# EAGLEPCBFINAL.net
KiCad netlist of a schematic drawn in EAGLE
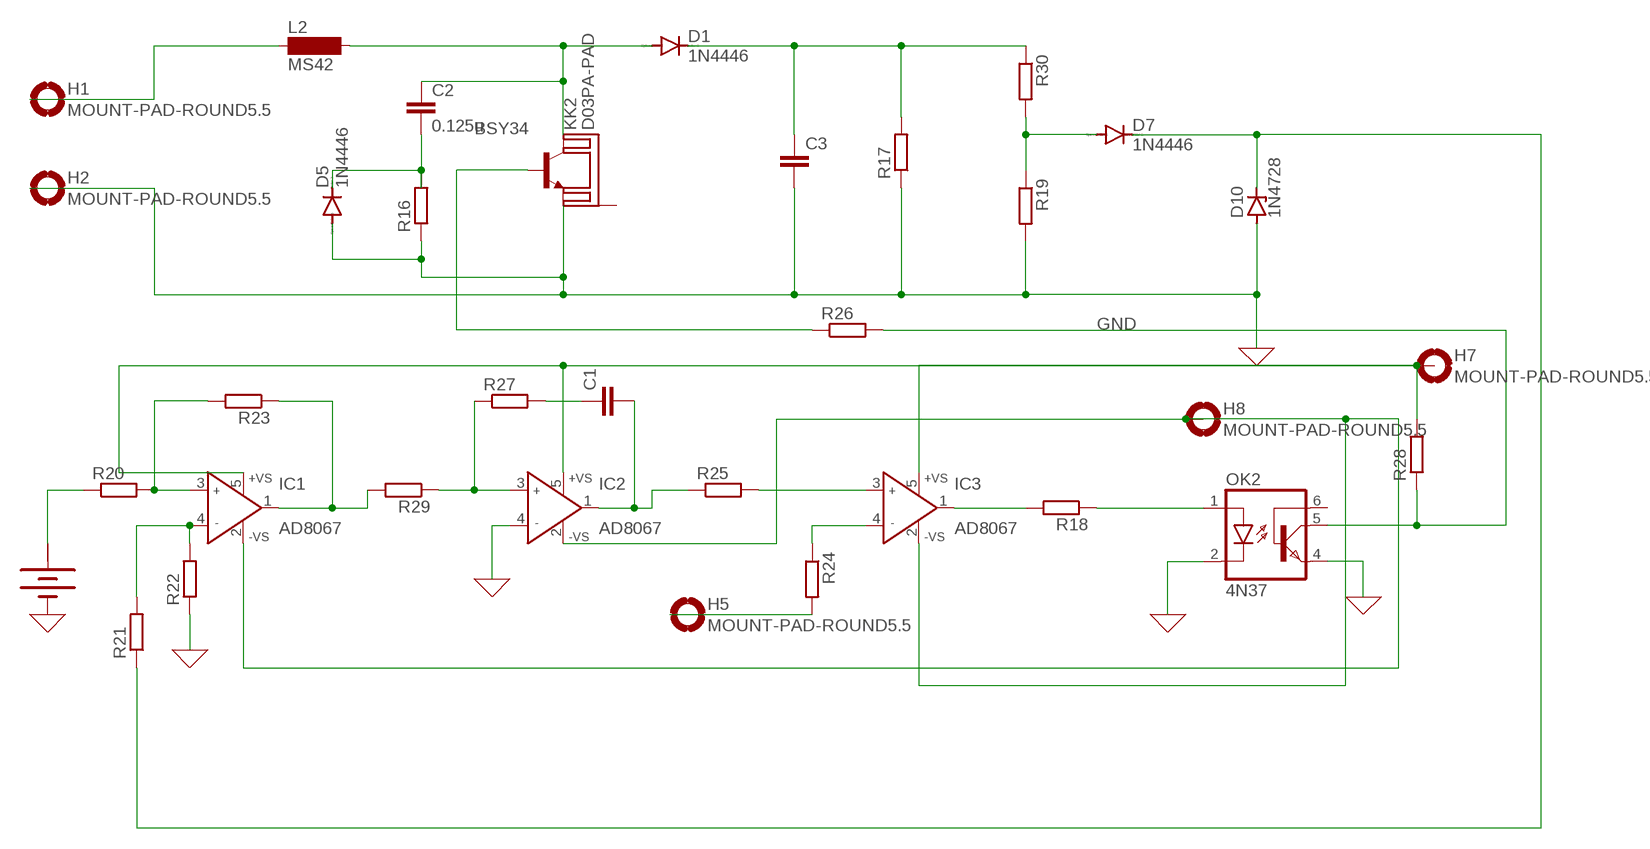
[diagram p0: schematic, sheet 1]

(export (version "E")
  (design (tool "Eeschema 10.0.6"))
  (components
    (comp (ref "BAT1")
      (value "BATTERY")
      (footprint "eagle-import:BATTERY")
      (libsource (lib "eagle-import") (part "BATTERY"))
    )
    (comp (ref "C1")
      (value "C2.5/2")
      (footprint "eagle-import:C2.5-2")
      (libsource (lib "eagle-import") (part "C2.5/2"))
    )
    (comp (ref "C2")
      (value "0.125u")
      (footprint "eagle-import:C5B3.5")
      (libsource (lib "eagle-import") (part "C5/3.5"))
    )
    (comp (ref "C3")
      (value "C7.5/3")
      (footprint "eagle-import:C7.5B3")
      (libsource (lib "eagle-import") (part "C7.5/3"))
    )
    (comp (ref "D1")
      (value "1N4446")
      (footprint "eagle-import:DO35-10")
      (libsource (lib "eagle-import") (part "1N4446"))
    )
    (comp (ref "D5")
      (value "1N4446")
      (footprint "eagle-import:DO35-10")
      (libsource (lib "eagle-import") (part "1N4446"))
    )
    (comp (ref "D7")
      (value "1N4446")
      (footprint "eagle-import:DO35-10")
      (libsource (lib "eagle-import") (part "1N4446"))
    )
    (comp (ref "D10")
      (value "1N4728")
      (footprint "eagle-import:DO41Z10")
      (libsource (lib "eagle-import") (part "1N4728"))
    )
    (comp (ref "H1")
      (value "MOUNT-PAD-ROUND5.5")
      (footprint "eagle-import:5,5-PAD")
      (libsource (lib "eagle-import") (part "MOUNT-PAD-ROUND5.5"))
    )
    (comp (ref "H2")
      (value "MOUNT-PAD-ROUND5.5")
      (footprint "eagle-import:5,5-PAD")
      (libsource (lib "eagle-import") (part "MOUNT-PAD-ROUND5.5"))
    )
    (comp (ref "H5")
      (value "MOUNT-PAD-ROUND5.5")
      (footprint "eagle-import:5,5-PAD")
      (libsource (lib "eagle-import") (part "MOUNT-PAD-ROUND5.5"))
    )
    (comp (ref "H7")
      (value "MOUNT-PAD-ROUND5.5")
      (footprint "eagle-import:5,5-PAD")
      (libsource (lib "eagle-import") (part "MOUNT-PAD-ROUND5.5"))
    )
    (comp (ref "H8")
      (value "MOUNT-PAD-ROUND5.5")
      (footprint "eagle-import:5,5-PAD")
      (libsource (lib "eagle-import") (part "MOUNT-PAD-ROUND5.5"))
    )
    (comp (ref "IC1")
      (value "AD8067")
      (footprint "eagle-import:SOT23-5")
      (fields (field (name "MF") "ALTERA CORPORATION") (field (name "MPN") "AD8067ARTZ-REEL7"))
      (libsource (lib "eagle-import") (part "AD8067"))
    )
    (comp (ref "IC2")
      (value "AD8067")
      (footprint "eagle-import:SOT23-5")
      (fields (field (name "MF") "ALTERA CORPORATION") (field (name "MPN") "AD8067ARTZ-REEL7"))
      (libsource (lib "eagle-import") (part "AD8067"))
    )
    (comp (ref "IC3")
      (value "AD8067")
      (footprint "eagle-import:SOT23-5")
      (fields (field (name "MF") "ALTERA CORPORATION") (field (name "MPN") "AD8067ARTZ-REEL7"))
      (libsource (lib "eagle-import") (part "AD8067"))
    )
    (comp (ref "KK2")
      (value "D03PA-PAD")
      (footprint "eagle-import:D03PA-PAD")
      (libsource (lib "eagle-import") (part "D03PA-PAD"))
    )
    (comp (ref "L2")
      (value "MS42")
      (footprint "eagle-import:MS42")
      (libsource (lib "eagle-import") (part "MS42"))
    )
    (comp (ref "OK2")
      (value "4N37")
      (footprint "eagle-import:DIL06")
      (fields (field (name "MF") "FAIRCHILD SEMICONDUCTOR"))
      (libsource (lib "eagle-import") (part "4N37"))
    )
    (comp (ref "R16")
      (value "R-EU_0204/2V")
      (footprint "eagle-import:0204V")
      (libsource (lib "eagle-import") (part "R-EU_0204/2V"))
    )
    (comp (ref "R17")
      (value "R-EU_0204/2V")
      (footprint "eagle-import:0204V")
      (libsource (lib "eagle-import") (part "R-EU_0204/2V"))
    )
    (comp (ref "R18")
      (value "R-EU_0204/5")
      (footprint "eagle-import:0204_5")
      (libsource (lib "eagle-import") (part "R-EU_0204/5"))
    )
    (comp (ref "R19")
      (value "R-EU_0207/10")
      (footprint "eagle-import:0207_10")
      (libsource (lib "eagle-import") (part "R-EU_0207/10"))
    )
    (comp (ref "R20")
      (value "R-EU_0207/10")
      (footprint "eagle-import:0207_10")
      (libsource (lib "eagle-import") (part "R-EU_0207/10"))
    )
    (comp (ref "R21")
      (value "R-EU_0207/10")
      (footprint "eagle-import:0207_10")
      (libsource (lib "eagle-import") (part "R-EU_0207/10"))
    )
    (comp (ref "R22")
      (value "R-EU_0207/10")
      (footprint "eagle-import:0207_10")
      (libsource (lib "eagle-import") (part "R-EU_0207/10"))
    )
    (comp (ref "R23")
      (value "R-EU_0207/10")
      (footprint "eagle-import:0207_10")
      (libsource (lib "eagle-import") (part "R-EU_0207/10"))
    )
    (comp (ref "R24")
      (value "R-EU_0207/10")
      (footprint "eagle-import:0207_10")
      (libsource (lib "eagle-import") (part "R-EU_0207/10"))
    )
    (comp (ref "R25")
      (value "R-EU_0207/10")
      (footprint "eagle-import:0207_10")
      (libsource (lib "eagle-import") (part "R-EU_0207/10"))
    )
    (comp (ref "R26")
      (value "R-EU_0207/10")
      (footprint "eagle-import:0207_10")
      (libsource (lib "eagle-import") (part "R-EU_0207/10"))
    )
    (comp (ref "R27")
      (value "R-EU_0309/12")
      (footprint "eagle-import:0309_12")
      (libsource (lib "eagle-import") (part "R-EU_0309/12"))
    )
    (comp (ref "R28")
      (value "R-EU_0411/15")
      (footprint "eagle-import:0411_15")
      (libsource (lib "eagle-import") (part "R-EU_0411/15"))
    )
    (comp (ref "R29")
      (value "R-EU_0411/15")
      (footprint "eagle-import:0411_15")
      (libsource (lib "eagle-import") (part "R-EU_0411/15"))
    )
    (comp (ref "R30")
      (value "R-EU_0922/22")
      (footprint "eagle-import:0922_22")
      (libsource (lib "eagle-import") (part "R-EU_0922/22"))
    )
    (comp (ref "T1")
      (value "BSY34")
      (footprint "eagle-import:TO39")
      (libsource (lib "eagle-import") (part "BSY34"))
    )
  )
  (nets
    (net (code "1") (name "/+") (class "Default")
      (node (ref "BAT1") (pin "+@1") (pinfunction "+_+@1") (pintype "power_in"))
    )
    (net (code "2") (name "GND") (class "Default")
      (node (ref "BAT1") (pin "-") (pinfunction "-_-") (pintype "power_in"))
      (node (ref "C3") (pin "2") (pinfunction "2_2") (pintype "passive"))
      (node (ref "D10") (pin "A") (pinfunction "A_A") (pintype "passive"))
      (node (ref "D5") (pin "A") (pinfunction "A_A") (pintype "passive"))
      (node (ref "H2") (pin "B5,5") (pinfunction "MOUNT_B5,5") (pintype "passive"))
      (node (ref "IC2") (pin "4") (pinfunction "IN-_4") (pintype "input"))
      (node (ref "OK2") (pin "2") (pinfunction "C_2") (pintype "passive"))
      (node (ref "OK2") (pin "4") (pinfunction "EMI_4") (pintype "passive"))
      (node (ref "R16") (pin "1") (pinfunction "1_1") (pintype "passive"))
      (node (ref "R17") (pin "1") (pinfunction "1_1") (pintype "passive"))
      (node (ref "R19") (pin "2") (pinfunction "2_2") (pintype "passive"))
      (node (ref "R22") (pin "1") (pinfunction "1_1") (pintype "passive"))
      (node (ref "T1") (pin "1") (pinfunction "E_1") (pintype "passive"))
    )
    (net (code "3") (name "Net-(BAT1-Pad+)") (class "Default")
      (node (ref "BAT1") (pin "+") (pinfunction "+_+") (pintype "power_in"))
      (node (ref "R20") (pin "1") (pinfunction "1_1") (pintype "passive"))
    )
    (net (code "4") (name "Net-(C1-Pad1)") (class "Default")
      (node (ref "C1") (pin "1") (pinfunction "1_1") (pintype "passive"))
      (node (ref "R27") (pin "2") (pinfunction "2_2") (pintype "passive"))
    )
    (net (code "5") (name "Net-(C2-Pad2)") (class "Default")
      (node (ref "C2") (pin "2") (pinfunction "2_2") (pintype "passive"))
      (node (ref "D5") (pin "C") (pinfunction "C_C") (pintype "passive"))
      (node (ref "R16") (pin "2") (pinfunction "2_2") (pintype "passive"))
    )
    (net (code "6") (name "Net-(C3-Pad1)") (class "Default")
      (node (ref "C3") (pin "1") (pinfunction "1_1") (pintype "passive"))
      (node (ref "D1") (pin "C") (pinfunction "C_C") (pintype "passive"))
      (node (ref "R17") (pin "2") (pinfunction "2_2") (pintype "passive"))
      (node (ref "R30") (pin "1") (pinfunction "1_1") (pintype "passive"))
    )
    (net (code "7") (name "Net-(D7-PadA)") (class "Default")
      (node (ref "D7") (pin "A") (pinfunction "A_A") (pintype "passive"))
      (node (ref "R19") (pin "1") (pinfunction "1_1") (pintype "passive"))
      (node (ref "R30") (pin "2") (pinfunction "2_2") (pintype "passive"))
    )
    (net (code "8") (name "Net-(D10-PadC)") (class "Default")
      (node (ref "D10") (pin "C") (pinfunction "C_C") (pintype "passive"))
      (node (ref "D7") (pin "C") (pinfunction "C_C") (pintype "passive"))
      (node (ref "R21") (pin "1") (pinfunction "1_1") (pintype "passive"))
    )
    (net (code "9") (name "Net-(H1-MOUNT)") (class "Default")
      (node (ref "H1") (pin "B5,5") (pinfunction "MOUNT_B5,5") (pintype "passive"))
      (node (ref "L2") (pin "1") (pinfunction "1_1") (pintype "passive"))
    )
    (net (code "10") (name "Net-(H5-MOUNT)") (class "Default")
      (node (ref "H5") (pin "B5,5") (pinfunction "MOUNT_B5,5") (pintype "passive"))
      (node (ref "R24") (pin "2") (pinfunction "2_2") (pintype "passive"))
    )
    (net (code "11") (name "Net-(H7-MOUNT)") (class "Default")
      (node (ref "H7") (pin "B5,5") (pinfunction "MOUNT_B5,5") (pintype "passive"))
      (node (ref "IC1") (pin "5") (pinfunction "+VS_5") (pintype "input"))
      (node (ref "IC2") (pin "5") (pinfunction "+VS_5") (pintype "input"))
      (node (ref "IC3") (pin "5") (pinfunction "+VS_5") (pintype "input"))
      (node (ref "R28") (pin "2") (pinfunction "2_2") (pintype "passive"))
    )
    (net (code "12") (name "Net-(H8-MOUNT)") (class "Default")
      (node (ref "H8") (pin "B5,5") (pinfunction "MOUNT_B5,5") (pintype "passive"))
      (node (ref "IC1") (pin "2") (pinfunction "-VS_2") (pintype "input"))
      (node (ref "IC2") (pin "2") (pinfunction "-VS_2") (pintype "input"))
      (node (ref "IC3") (pin "2") (pinfunction "-VS_2") (pintype "input"))
    )
    (net (code "13") (name "Net-(IC1-IN+)") (class "Default")
      (node (ref "IC1") (pin "3") (pinfunction "IN+_3") (pintype "input"))
      (node (ref "R20") (pin "2") (pinfunction "2_2") (pintype "passive"))
      (node (ref "R23") (pin "2") (pinfunction "2_2") (pintype "passive"))
    )
    (net (code "14") (name "Net-(IC1-IN-)") (class "Default")
      (node (ref "IC1") (pin "4") (pinfunction "IN-_4") (pintype "input"))
      (node (ref "R21") (pin "2") (pinfunction "2_2") (pintype "passive"))
      (node (ref "R22") (pin "2") (pinfunction "2_2") (pintype "passive"))
    )
    (net (code "15") (name "Net-(IC1-OUT)") (class "Default")
      (node (ref "IC1") (pin "1") (pinfunction "OUT_1") (pintype "output"))
      (node (ref "R23") (pin "1") (pinfunction "1_1") (pintype "passive"))
      (node (ref "R29") (pin "2") (pinfunction "2_2") (pintype "passive"))
    )
    (net (code "16") (name "Net-(IC2-IN+)") (class "Default")
      (node (ref "IC2") (pin "3") (pinfunction "IN+_3") (pintype "input"))
      (node (ref "R27") (pin "1") (pinfunction "1_1") (pintype "passive"))
      (node (ref "R29") (pin "1") (pinfunction "1_1") (pintype "passive"))
    )
    (net (code "17") (name "Net-(IC2-OUT)") (class "Default")
      (node (ref "C1") (pin "2") (pinfunction "2_2") (pintype "passive"))
      (node (ref "IC2") (pin "1") (pinfunction "OUT_1") (pintype "output"))
      (node (ref "R25") (pin "1") (pinfunction "1_1") (pintype "passive"))
    )
    (net (code "18") (name "Net-(IC3-IN+)") (class "Default")
      (node (ref "IC3") (pin "3") (pinfunction "IN+_3") (pintype "input"))
      (node (ref "R25") (pin "2") (pinfunction "2_2") (pintype "passive"))
    )
    (net (code "19") (name "Net-(IC3-IN-)") (class "Default")
      (node (ref "IC3") (pin "4") (pinfunction "IN-_4") (pintype "input"))
      (node (ref "R24") (pin "1") (pinfunction "1_1") (pintype "passive"))
    )
    (net (code "20") (name "Net-(IC3-OUT)") (class "Default")
      (node (ref "IC3") (pin "1") (pinfunction "OUT_1") (pintype "output"))
      (node (ref "R18") (pin "2") (pinfunction "2_2") (pintype "passive"))
    )
    (net (code "21") (name "Net-(OK2-A)") (class "Default")
      (node (ref "OK2") (pin "1") (pinfunction "A_1") (pintype "passive"))
      (node (ref "R18") (pin "1") (pinfunction "1_1") (pintype "passive"))
    )
    (net (code "22") (name "Net-(OK2-COL)") (class "Default")
      (node (ref "OK2") (pin "5") (pinfunction "COL_5") (pintype "passive"))
      (node (ref "R26") (pin "2") (pinfunction "2_2") (pintype "passive"))
      (node (ref "R28") (pin "1") (pinfunction "1_1") (pintype "passive"))
    )
    (net (code "23") (name "Net-(T1-B)") (class "Default")
      (node (ref "R26") (pin "1") (pinfunction "1_1") (pintype "passive"))
      (node (ref "T1") (pin "2") (pinfunction "B_2") (pintype "passive"))
    )
    (net (code "24") (name "Net-(T1-C)") (class "Default")
      (node (ref "C2") (pin "1") (pinfunction "1_1") (pintype "passive"))
      (node (ref "D1") (pin "A") (pinfunction "A_A") (pintype "passive"))
      (node (ref "L2") (pin "2") (pinfunction "2_2") (pintype "passive"))
      (node (ref "T1") (pin "3") (pinfunction "C_3") (pintype "passive"))
    )
    (net (code "25") (name "unconnected-(KK2-K-PadB)") (class "Default")
      (node (ref "KK2") (pin "B") (pinfunction "K_B") (pintype "passive"))
    )
    (net (code "26") (name "unconnected-(OK2-BAS-Pad6)") (class "Default")
      (node (ref "OK2") (pin "6") (pinfunction "BAS_6") (pintype "passive"))
    )
  )
)
